# ProPrj_RF_Nano_Funbots_2025-01-09.net
KiCad netlist of a schematic drawn in EasyEDA Pro
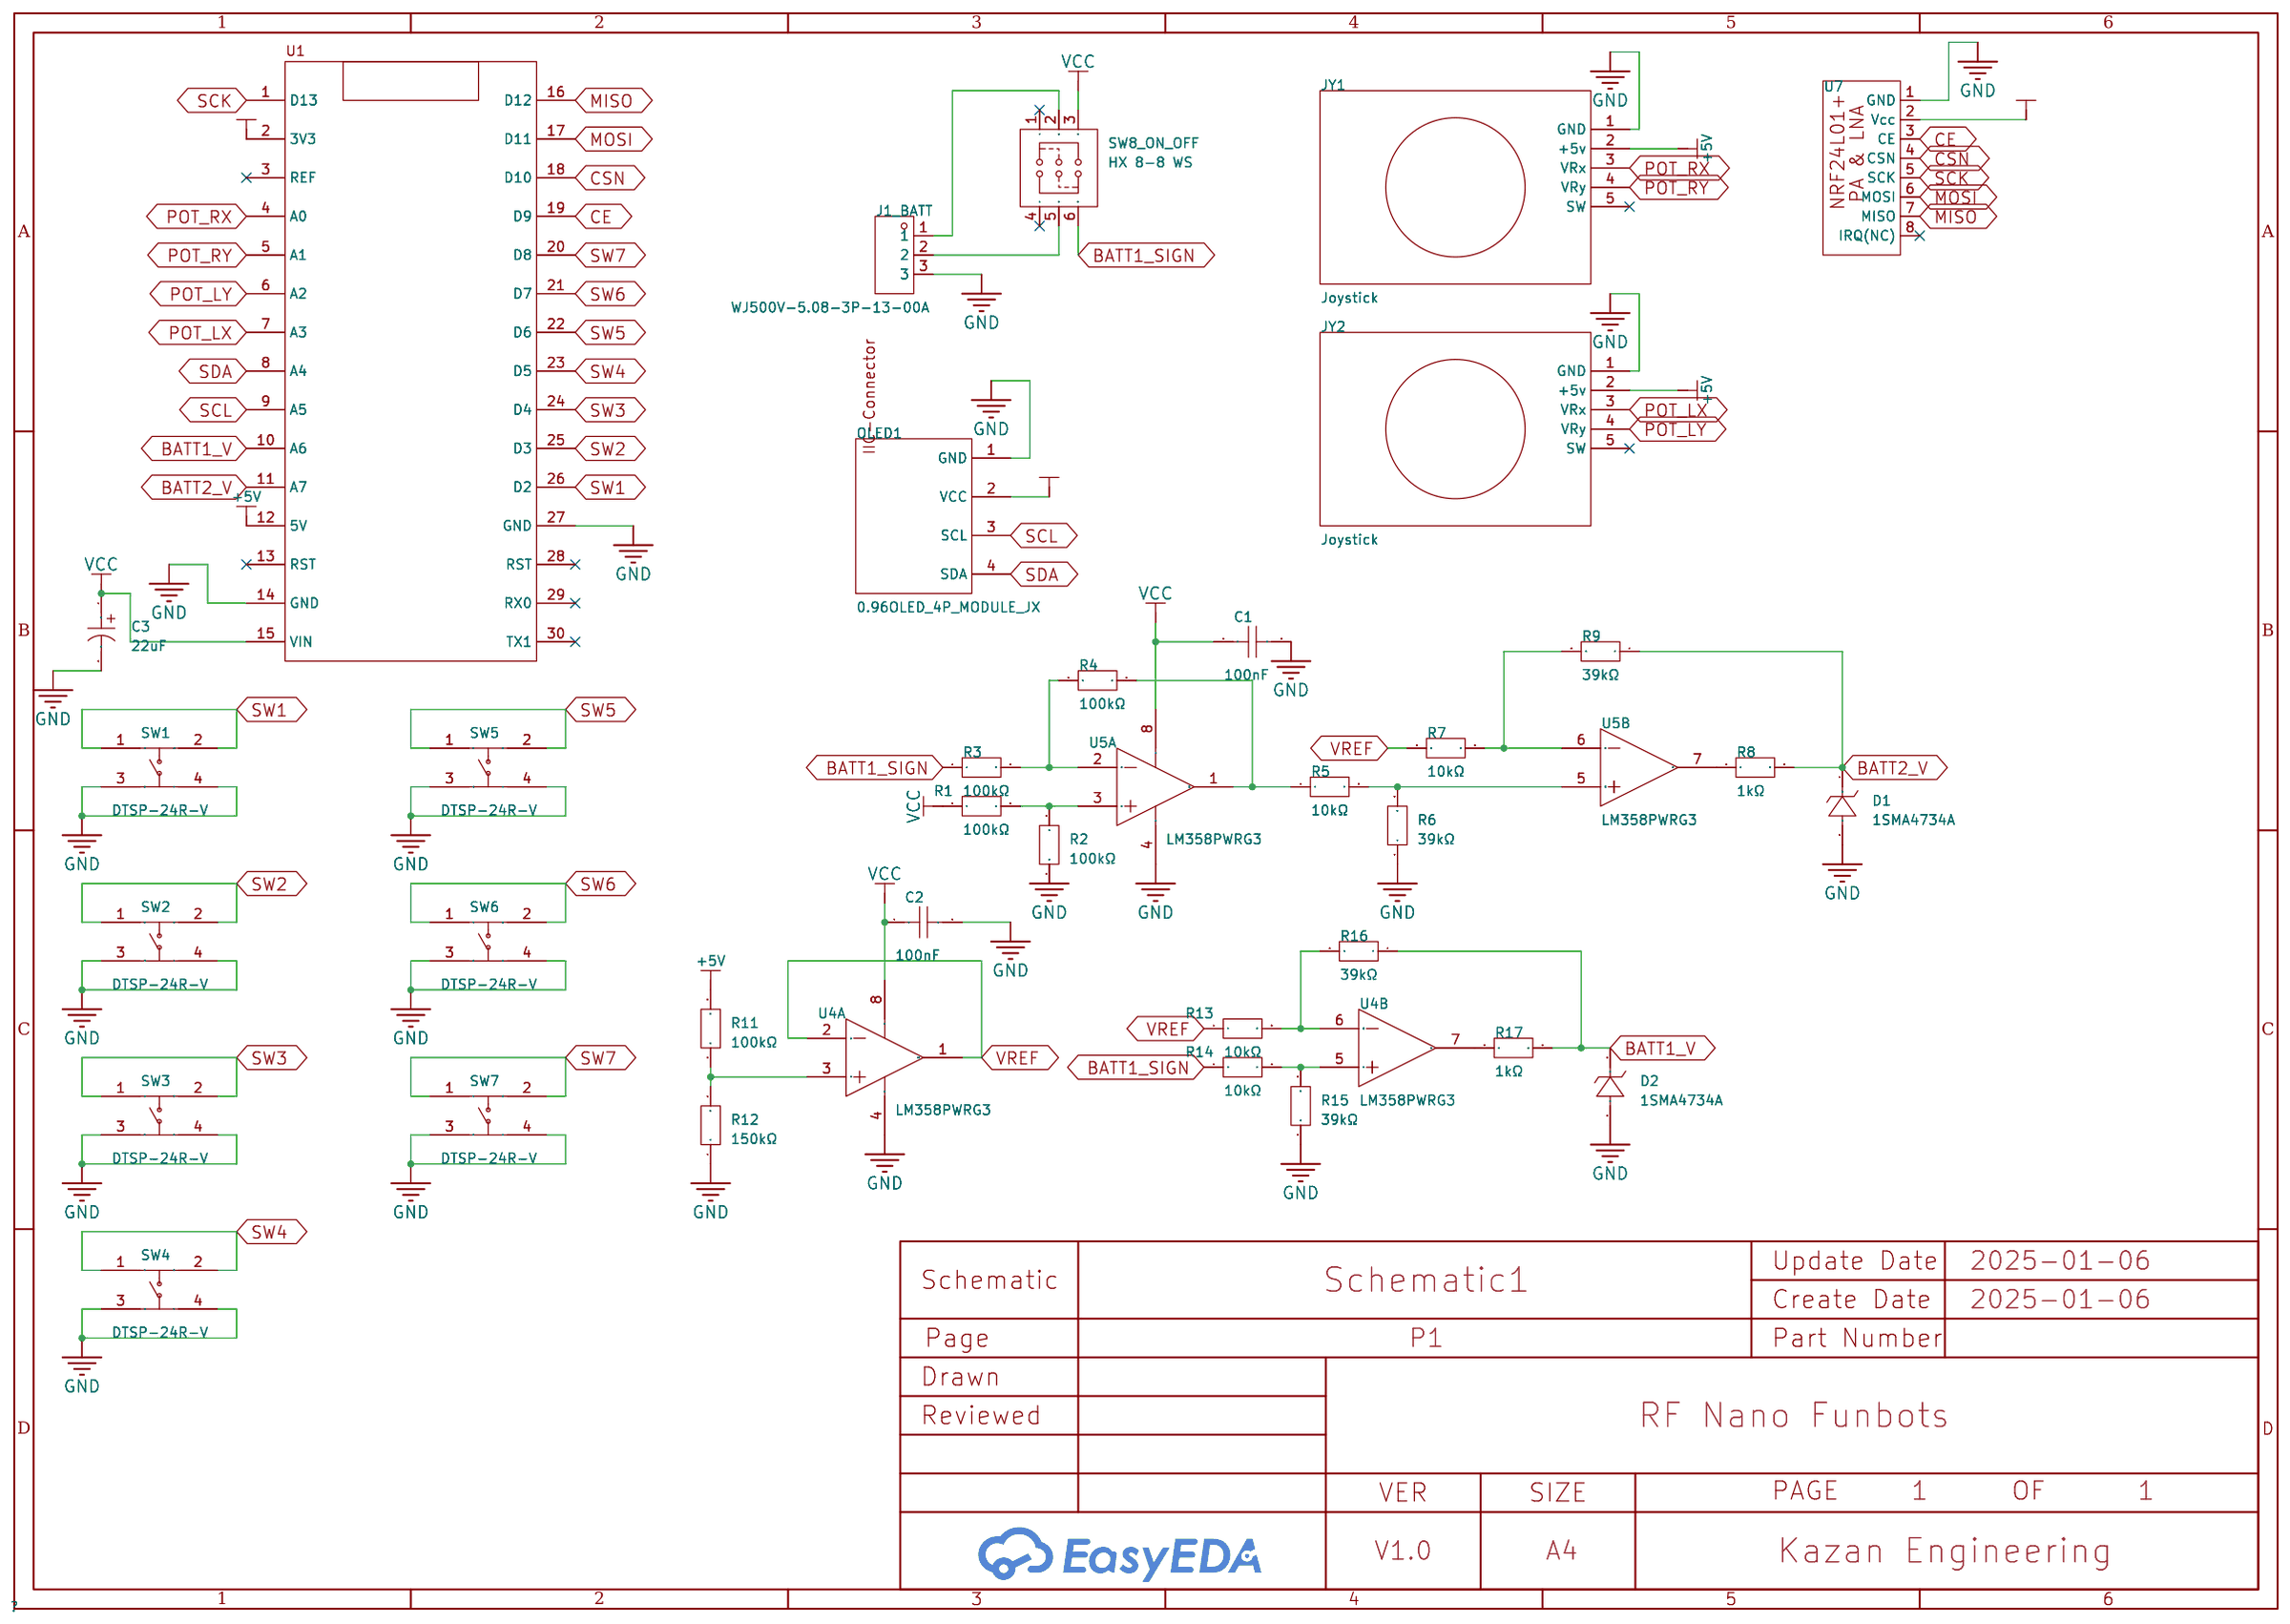
[diagram p0: schematic sheet]

(export (version "E")
  (design (tool "Eeschema 10.0.6"))
  (components
    (comp (ref "C1")
      (value "100nF")
      (footprint "easyedapro:C0805")
      (fields
        (field (name "Manufacturer Part") "FCC0805B104K500DT")
        (field (name "Manufacturer") "FOJAN(富捷)")
      )
      (libsource (lib "easyedapro") (part "FCC0805B104K500DT"))
    )
    (comp (ref "C2")
      (value "100nF")
      (footprint "easyedapro:C0805")
      (fields
        (field (name "Manufacturer Part") "FCC0805B104K500DT")
        (field (name "Manufacturer") "FOJAN(富捷)")
      )
      (libsource (lib "easyedapro") (part "FCC0805B104K500DT"))
    )
    (comp (ref "C3")
      (value "22uF")
      (footprint "easyedapro:CAP-TH_BD5.0-P2.00-D0.5-FD")
      (fields (field (name "Manufacturer Part") "CD1101HM220D110T") (field (name "Manufacturer") "创慧电子"))
      (libsource (lib "easyedapro") (part "CD1101HM220D110T"))
    )
    (comp (ref "D1")
      (value "1SMA4734A")
      (footprint "easyedapro:SMA_L4.3-W2.6-LS5.1-RD")
      (fields (field (name "Manufacturer") "YONGYUTAI(永裕泰)"))
      (libsource (lib "easyedapro") (part "1SMA4734A_C5128847"))
    )
    (comp (ref "D2")
      (value "1SMA4734A")
      (footprint "easyedapro:SMA_L4.3-W2.6-LS5.1-RD")
      (fields (field (name "Manufacturer") "YONGYUTAI(永裕泰)"))
      (libsource (lib "easyedapro") (part "1SMA4734A_C5128847"))
    )
    (comp (ref "J1_BATT")
      (value "WJ500V-5.08-3P-13-00A")
      (footprint "easyedapro:CONN-TH_3P-P5.00_WJ500V-5.08-3P")
      (fields (field (name "Manufacturer") "KANGNEX(康奈克斯电气)"))
      (libsource (lib "easyedapro") (part "WJ500V-5.08-3P-13-00A"))
    )
    (comp (ref "JY1")
      (value "Joystick")
      (footprint "easyedapro:JOYSTICK-2AXIS-BUTTON")
      (libsource (lib "easyedapro") (part "JoyStick_Arduino"))
    )
    (comp (ref "JY2")
      (value "Joystick")
      (footprint "easyedapro:JOYSTICK-2AXIS-BUTTON")
      (libsource (lib "easyedapro") (part "JoyStick_Arduino"))
    )
    (comp (ref "OLED1")
      (value "0.96OLED_4P_MODULE_JX")
      (footprint "easyedapro:0.96OLED_4P")
      (libsource (lib "easyedapro") (part "0.96OLED_4P_MODULE_JX"))
    )
    (comp (ref "R1")
      (value "100kΩ")
      (footprint "easyedapro:R0402")
      (fields
        (field (name "Manufacturer Part") "ERA-2VEB1003X")
        (field (name "Manufacturer") "PANASONIC(松下)")
      )
      (libsource (lib "easyedapro") (part "ERA-2VEB1003X"))
    )
    (comp (ref "R2")
      (value "100kΩ")
      (footprint "easyedapro:R0402")
      (fields
        (field (name "Manufacturer Part") "ERA-2VEB1003X")
        (field (name "Manufacturer") "PANASONIC(松下)")
      )
      (libsource (lib "easyedapro") (part "ERA-2VEB1003X"))
    )
    (comp (ref "R3")
      (value "100kΩ")
      (footprint "easyedapro:R0402")
      (fields
        (field (name "Manufacturer Part") "ERA-2VEB1003X")
        (field (name "Manufacturer") "PANASONIC(松下)")
      )
      (libsource (lib "easyedapro") (part "ERA-2VEB1003X"))
    )
    (comp (ref "R4")
      (value "100kΩ")
      (footprint "easyedapro:R0402")
      (fields
        (field (name "Manufacturer Part") "ERA-2VEB1003X")
        (field (name "Manufacturer") "PANASONIC(松下)")
      )
      (libsource (lib "easyedapro") (part "ERA-2VEB1003X"))
    )
    (comp (ref "R5")
      (value "10kΩ")
      (footprint "easyedapro:R1206")
      (fields (field (name "Manufacturer Part") "FRQ1206J103 TS") (field (name "Manufacturer") "FOJAN(富捷)"))
      (libsource (lib "easyedapro") (part "FRQ1206J103 TS"))
    )
    (comp (ref "R6")
      (value "39kΩ")
      (footprint "easyedapro:R1206")
      (fields (field (name "Manufacturer Part") "RT1206BRD0739KL") (field (name "Manufacturer") "YAGEO(国巨)"))
      (libsource (lib "easyedapro") (part "RT1206BRD0739KL"))
    )
    (comp (ref "R7")
      (value "10kΩ")
      (footprint "easyedapro:R1206")
      (fields (field (name "Manufacturer Part") "FRQ1206J103 TS") (field (name "Manufacturer") "FOJAN(富捷)"))
      (libsource (lib "easyedapro") (part "FRQ1206J103 TS"))
    )
    (comp (ref "R8")
      (value "1kΩ")
      (footprint "easyedapro:R0402")
      (fields (field (name "Manufacturer Part") "AC0402FR-7W1KL") (field (name "Manufacturer") "YAGEO(国巨)"))
      (libsource (lib "easyedapro") (part "AC0402FR-7W1KL"))
    )
    (comp (ref "R9")
      (value "39kΩ")
      (footprint "easyedapro:R1206")
      (fields (field (name "Manufacturer Part") "RT1206BRD0739KL") (field (name "Manufacturer") "YAGEO(国巨)"))
      (libsource (lib "easyedapro") (part "RT1206BRD0739KL"))
    )
    (comp (ref "R11")
      (value "100kΩ")
      (footprint "easyedapro:R0402")
      (fields
        (field (name "Manufacturer Part") "ERA-2VEB1003X")
        (field (name "Manufacturer") "PANASONIC(松下)")
      )
      (libsource (lib "easyedapro") (part "ERA-2VEB1003X"))
    )
    (comp (ref "R12")
      (value "150kΩ")
      (footprint "easyedapro:R0603")
      (fields (field (name "Manufacturer Part") "FRC0603F1503TS") (field (name "Manufacturer") "FOJAN(富捷)"))
      (libsource (lib "easyedapro") (part "FRC0603F1503TS"))
    )
    (comp (ref "R13")
      (value "10kΩ")
      (footprint "easyedapro:R1206")
      (fields (field (name "Manufacturer Part") "FRQ1206J103 TS") (field (name "Manufacturer") "FOJAN(富捷)"))
      (libsource (lib "easyedapro") (part "FRQ1206J103 TS"))
    )
    (comp (ref "R14")
      (value "10kΩ")
      (footprint "easyedapro:R1206")
      (fields (field (name "Manufacturer Part") "FRQ1206J103 TS") (field (name "Manufacturer") "FOJAN(富捷)"))
      (libsource (lib "easyedapro") (part "FRQ1206J103 TS"))
    )
    (comp (ref "R15")
      (value "39kΩ")
      (footprint "easyedapro:R1206")
      (fields (field (name "Manufacturer Part") "RT1206BRD0739KL") (field (name "Manufacturer") "YAGEO(国巨)"))
      (libsource (lib "easyedapro") (part "RT1206BRD0739KL"))
    )
    (comp (ref "R16")
      (value "39kΩ")
      (footprint "easyedapro:R1206")
      (fields (field (name "Manufacturer Part") "RT1206BRD0739KL") (field (name "Manufacturer") "YAGEO(国巨)"))
      (libsource (lib "easyedapro") (part "RT1206BRD0739KL"))
    )
    (comp (ref "R17")
      (value "1kΩ")
      (footprint "easyedapro:R0402")
      (fields (field (name "Manufacturer Part") "AC0402FR-7W1KL") (field (name "Manufacturer") "YAGEO(国巨)"))
      (libsource (lib "easyedapro") (part "AC0402FR-7W1KL"))
    )
    (comp (ref "SW1")
      (value "DTSP-24R-V")
      (footprint "easyedapro:SW-TH_4P-L12.0-W12.0-P5.00-LS13.0-EH")
      (libsource (lib "easyedapro") (part "DTSP-24R-V"))
    )
    (comp (ref "SW2")
      (value "DTSP-24R-V")
      (footprint "easyedapro:SW-TH_4P-L12.0-W12.0-P5.00-LS13.0-EH")
      (libsource (lib "easyedapro") (part "DTSP-24R-V"))
    )
    (comp (ref "SW3")
      (value "DTSP-24R-V")
      (footprint "easyedapro:SW-TH_4P-L12.0-W12.0-P5.00-LS13.0-EH")
      (libsource (lib "easyedapro") (part "DTSP-24R-V"))
    )
    (comp (ref "SW4")
      (value "DTSP-24R-V")
      (footprint "easyedapro:SW-TH_4P-L12.0-W12.0-P5.00-LS13.0-EH")
      (libsource (lib "easyedapro") (part "DTSP-24R-V"))
    )
    (comp (ref "SW5")
      (value "DTSP-24R-V")
      (footprint "easyedapro:SW-TH_4P-L12.0-W12.0-P5.00-LS13.0-EH")
      (libsource (lib "easyedapro") (part "DTSP-24R-V"))
    )
    (comp (ref "SW6")
      (value "DTSP-24R-V")
      (footprint "easyedapro:SW-TH_4P-L12.0-W12.0-P5.00-LS13.0-EH")
      (libsource (lib "easyedapro") (part "DTSP-24R-V"))
    )
    (comp (ref "SW7")
      (value "DTSP-24R-V")
      (footprint "easyedapro:SW-TH_4P-L12.0-W12.0-P5.00-LS13.0-EH")
      (libsource (lib "easyedapro") (part "DTSP-24R-V"))
    )
    (comp (ref "SW8_ON_OFF")
      (value "HX 8-8 WS")
      (footprint "easyedapro:SW-TH_HX-8-8-WS")
      (fields (field (name "Manufacturer") "hanxia(韩下)"))
      (libsource (lib "easyedapro") (part "HX 8-8 WS"))
    )
    (comp (ref "U1")
      (value "~")
      (footprint "easyedapro:COMM-TH_ARDUINO_NANO")
      (description "Arduino Nano")
      (libsource (lib "easyedapro") (part "Arduino Nano"))
    )
    (comp (ref "U4")
      (value "LM358PWRG3")
      (footprint "easyedapro:TSSOP-8_L4.4-W3.0-P0.65-LS6.4-BL")
      (fields (field (name "Manufacturer") "TI(德州仪器)"))
      (libsource (lib "easyedapro") (part "LM358PWRG3"))
    )
    (comp (ref "U5")
      (value "LM358PWRG3")
      (footprint "easyedapro:TSSOP-8_L4.4-W3.0-P0.65-LS6.4-BL")
      (fields (field (name "Manufacturer") "TI(德州仪器)"))
      (libsource (lib "easyedapro") (part "LM358PWRG3"))
    )
    (comp (ref "U7")
      (value "~")
      (footprint "easyedapro:NRF24L01+PA+LNA_PCB")
      (libsource (lib "easyedapro") (part "NRF24L01+PA+LNA"))
    )
  )
  (nets
    (net (code "1") (name "+3.3V") (class "Default")
      (node (ref "OLED1") (pin "2") (pinfunction "VCC_2") (pintype "input"))
      (node (ref "U1") (pin "2") (pinfunction "3V3_2") (pintype "input"))
      (node (ref "U7") (pin "2") (pinfunction "Vcc_2") (pintype "unspecified"))
    )
    (net (code "2") (name "+5V") (class "Default")
      (node (ref "JY1") (pin "2") (pinfunction "+5v_2") (pintype "input"))
      (node (ref "JY2") (pin "2") (pinfunction "+5v_2") (pintype "input"))
      (node (ref "R11") (pin "2") (pinfunction "2_2") (pintype "unspecified"))
      (node (ref "U1") (pin "12") (pinfunction "5V_12") (pintype "input"))
    )
    (net (code "3") (name "BATT1_SIGN") (class "Default")
      (node (ref "R14") (pin "1") (pinfunction "1_1") (pintype "unspecified"))
      (node (ref "R3") (pin "1") (pinfunction "1_1") (pintype "unspecified"))
      (node (ref "SW8_ON_OFF") (pin "6") (pinfunction "6_6") (pintype "unspecified"))
    )
    (net (code "4") (name "BATT1_V") (class "Default")
      (node (ref "D2") (pin "1") (pinfunction "C_1") (pintype "unspecified"))
      (node (ref "R16") (pin "1") (pinfunction "1_1") (pintype "unspecified"))
      (node (ref "R17") (pin "2") (pinfunction "2_2") (pintype "unspecified"))
      (node (ref "U1") (pin "10") (pinfunction "A6_10") (pintype "input"))
    )
    (net (code "5") (name "BATT2_V") (class "Default")
      (node (ref "D1") (pin "1") (pinfunction "C_1") (pintype "unspecified"))
      (node (ref "R8") (pin "2") (pinfunction "2_2") (pintype "unspecified"))
      (node (ref "R9") (pin "1") (pinfunction "1_1") (pintype "unspecified"))
      (node (ref "U1") (pin "11") (pinfunction "A7_11") (pintype "input"))
    )
    (net (code "6") (name "CE") (class "Default")
      (node (ref "U1") (pin "19") (pinfunction "D9_19") (pintype "input"))
      (node (ref "U7") (pin "3") (pinfunction "CE_3") (pintype "unspecified"))
    )
    (net (code "7") (name "CSN") (class "Default")
      (node (ref "U1") (pin "18") (pinfunction "D10_18") (pintype "input"))
      (node (ref "U7") (pin "4") (pinfunction "CSN_4") (pintype "unspecified"))
    )
    (net (code "8") (name "GND") (class "Default")
      (node (ref "C1") (pin "2") (pinfunction "2_2") (pintype "unspecified"))
      (node (ref "C2") (pin "2") (pinfunction "2_2") (pintype "unspecified"))
      (node (ref "C3") (pin "2") (pinfunction "2_2") (pintype "input"))
      (node (ref "D1") (pin "2") (pinfunction "A_2") (pintype "unspecified"))
      (node (ref "D2") (pin "2") (pinfunction "A_2") (pintype "unspecified"))
      (node (ref "J1_BATT") (pin "3") (pinfunction "3_3") (pintype "unspecified"))
      (node (ref "JY1") (pin "1") (pinfunction "GND_1") (pintype "input"))
      (node (ref "JY2") (pin "1") (pinfunction "GND_1") (pintype "input"))
      (node (ref "OLED1") (pin "1") (pinfunction "GND_1") (pintype "input"))
      (node (ref "R12") (pin "1") (pinfunction "1_1") (pintype "unspecified"))
      (node (ref "R15") (pin "1") (pinfunction "1_1") (pintype "unspecified"))
      (node (ref "R2") (pin "1") (pinfunction "1_1") (pintype "unspecified"))
      (node (ref "R6") (pin "1") (pinfunction "1_1") (pintype "unspecified"))
      (node (ref "SW1") (pin "3") (pinfunction "3_3") (pintype "unspecified"))
      (node (ref "SW1") (pin "4") (pinfunction "4_4") (pintype "unspecified"))
      (node (ref "SW2") (pin "3") (pinfunction "3_3") (pintype "unspecified"))
      (node (ref "SW2") (pin "4") (pinfunction "4_4") (pintype "unspecified"))
      (node (ref "SW3") (pin "3") (pinfunction "3_3") (pintype "unspecified"))
      (node (ref "SW3") (pin "4") (pinfunction "4_4") (pintype "unspecified"))
      (node (ref "SW4") (pin "3") (pinfunction "3_3") (pintype "unspecified"))
      (node (ref "SW4") (pin "4") (pinfunction "4_4") (pintype "unspecified"))
      (node (ref "SW5") (pin "3") (pinfunction "3_3") (pintype "unspecified"))
      (node (ref "SW5") (pin "4") (pinfunction "4_4") (pintype "unspecified"))
      (node (ref "SW6") (pin "3") (pinfunction "3_3") (pintype "unspecified"))
      (node (ref "SW6") (pin "4") (pinfunction "4_4") (pintype "unspecified"))
      (node (ref "SW7") (pin "3") (pinfunction "3_3") (pintype "unspecified"))
      (node (ref "SW7") (pin "4") (pinfunction "4_4") (pintype "unspecified"))
      (node (ref "U1") (pin "14") (pinfunction "GND_14") (pintype "input"))
      (node (ref "U1") (pin "27") (pinfunction "GND_27") (pintype "input"))
      (node (ref "U4") (pin "4") (pinfunction "V-_4") (pintype "unspecified"))
      (node (ref "U5") (pin "4") (pinfunction "V-_4") (pintype "unspecified"))
      (node (ref "U7") (pin "1") (pinfunction "GND_1") (pintype "unspecified"))
    )
    (net (code "9") (name "MISO") (class "Default")
      (node (ref "U1") (pin "16") (pinfunction "D12_16") (pintype "input"))
      (node (ref "U7") (pin "7") (pinfunction "MISO_7") (pintype "unspecified"))
    )
    (net (code "10") (name "MOSI") (class "Default")
      (node (ref "U1") (pin "17") (pinfunction "D11_17") (pintype "input"))
      (node (ref "U7") (pin "6") (pinfunction "MOSI_6") (pintype "unspecified"))
    )
    (net (code "11") (name "Net-(J1_BATT-Pad1)") (class "Default")
      (node (ref "J1_BATT") (pin "1") (pinfunction "1_1") (pintype "unspecified"))
      (node (ref "SW8_ON_OFF") (pin "2") (pinfunction "2_2") (pintype "unspecified"))
    )
    (net (code "12") (name "Net-(J1_BATT-Pad2)") (class "Default")
      (node (ref "J1_BATT") (pin "2") (pinfunction "2_2") (pintype "unspecified"))
      (node (ref "SW8_ON_OFF") (pin "5") (pinfunction "5_5") (pintype "unspecified"))
    )
    (net (code "13") (name "Net-(U4A-IN1+)") (class "Default")
      (node (ref "R11") (pin "1") (pinfunction "1_1") (pintype "unspecified"))
      (node (ref "R12") (pin "2") (pinfunction "2_2") (pintype "unspecified"))
      (node (ref "U4") (pin "3") (pinfunction "IN1+_3") (pintype "unspecified"))
    )
    (net (code "14") (name "Net-(U4B-IN2+)") (class "Default")
      (node (ref "R14") (pin "2") (pinfunction "2_2") (pintype "unspecified"))
      (node (ref "R15") (pin "2") (pinfunction "2_2") (pintype "unspecified"))
      (node (ref "U4") (pin "5") (pinfunction "IN2+_5") (pintype "unspecified"))
    )
    (net (code "15") (name "Net-(U4B-IN2-)") (class "Default")
      (node (ref "R13") (pin "2") (pinfunction "2_2") (pintype "unspecified"))
      (node (ref "R16") (pin "2") (pinfunction "2_2") (pintype "unspecified"))
      (node (ref "U4") (pin "6") (pinfunction "IN2-_6") (pintype "unspecified"))
    )
    (net (code "16") (name "Net-(U4B-OUT2)") (class "Default")
      (node (ref "R17") (pin "1") (pinfunction "1_1") (pintype "unspecified"))
      (node (ref "U4") (pin "7") (pinfunction "OUT2_7") (pintype "unspecified"))
    )
    (net (code "17") (name "Net-(U5A-IN1+)") (class "Default")
      (node (ref "R1") (pin "2") (pinfunction "2_2") (pintype "unspecified"))
      (node (ref "R2") (pin "2") (pinfunction "2_2") (pintype "unspecified"))
      (node (ref "U5") (pin "3") (pinfunction "IN1+_3") (pintype "unspecified"))
    )
    (net (code "18") (name "Net-(U5A-IN1-)") (class "Default")
      (node (ref "R3") (pin "2") (pinfunction "2_2") (pintype "unspecified"))
      (node (ref "R4") (pin "1") (pinfunction "1_1") (pintype "unspecified"))
      (node (ref "U5") (pin "2") (pinfunction "IN1-_2") (pintype "unspecified"))
    )
    (net (code "19") (name "Net-(U5A-OUT1)") (class "Default")
      (node (ref "R4") (pin "2") (pinfunction "2_2") (pintype "unspecified"))
      (node (ref "R5") (pin "1") (pinfunction "1_1") (pintype "unspecified"))
      (node (ref "U5") (pin "1") (pinfunction "OUT1_1") (pintype "unspecified"))
    )
    (net (code "20") (name "Net-(U5B-IN2+)") (class "Default")
      (node (ref "R5") (pin "2") (pinfunction "2_2") (pintype "unspecified"))
      (node (ref "R6") (pin "2") (pinfunction "2_2") (pintype "unspecified"))
      (node (ref "U5") (pin "5") (pinfunction "IN2+_5") (pintype "unspecified"))
    )
    (net (code "21") (name "Net-(U5B-IN2-)") (class "Default")
      (node (ref "R7") (pin "2") (pinfunction "2_2") (pintype "unspecified"))
      (node (ref "R9") (pin "2") (pinfunction "2_2") (pintype "unspecified"))
      (node (ref "U5") (pin "6") (pinfunction "IN2-_6") (pintype "unspecified"))
    )
    (net (code "22") (name "Net-(U5B-OUT2)") (class "Default")
      (node (ref "R8") (pin "1") (pinfunction "1_1") (pintype "unspecified"))
      (node (ref "U5") (pin "7") (pinfunction "OUT2_7") (pintype "unspecified"))
    )
    (net (code "23") (name "POT_LX") (class "Default")
      (node (ref "JY2") (pin "3") (pinfunction "VRx_3") (pintype "input"))
      (node (ref "U1") (pin "7") (pinfunction "A3_7") (pintype "input"))
    )
    (net (code "24") (name "POT_LY") (class "Default")
      (node (ref "JY2") (pin "4") (pinfunction "VRy_4") (pintype "input"))
      (node (ref "U1") (pin "6") (pinfunction "A2_6") (pintype "input"))
    )
    (net (code "25") (name "POT_RX") (class "Default")
      (node (ref "JY1") (pin "3") (pinfunction "VRx_3") (pintype "input"))
      (node (ref "U1") (pin "4") (pinfunction "A0_4") (pintype "input"))
    )
    (net (code "26") (name "POT_RY") (class "Default")
      (node (ref "JY1") (pin "4") (pinfunction "VRy_4") (pintype "input"))
      (node (ref "U1") (pin "5") (pinfunction "A1_5") (pintype "input"))
    )
    (net (code "27") (name "SCK") (class "Default")
      (node (ref "U1") (pin "1") (pinfunction "D13_1") (pintype "input"))
      (node (ref "U7") (pin "5") (pinfunction "SCK_5") (pintype "unspecified"))
    )
    (net (code "28") (name "SCL") (class "Default")
      (node (ref "OLED1") (pin "3") (pinfunction "SCL_3") (pintype "input"))
      (node (ref "U1") (pin "9") (pinfunction "A5_9") (pintype "input"))
    )
    (net (code "29") (name "SDA") (class "Default")
      (node (ref "OLED1") (pin "4") (pinfunction "SDA_4") (pintype "input"))
      (node (ref "U1") (pin "8") (pinfunction "A4_8") (pintype "input"))
    )
    (net (code "30") (name "SW1") (class "Default")
      (node (ref "SW1") (pin "1") (pinfunction "1_1") (pintype "unspecified"))
      (node (ref "SW1") (pin "2") (pinfunction "2_2") (pintype "unspecified"))
      (node (ref "U1") (pin "26") (pinfunction "D2_26") (pintype "input"))
    )
    (net (code "31") (name "SW2") (class "Default")
      (node (ref "SW2") (pin "1") (pinfunction "1_1") (pintype "unspecified"))
      (node (ref "SW2") (pin "2") (pinfunction "2_2") (pintype "unspecified"))
      (node (ref "U1") (pin "25") (pinfunction "D3_25") (pintype "input"))
    )
    (net (code "32") (name "SW3") (class "Default")
      (node (ref "SW3") (pin "1") (pinfunction "1_1") (pintype "unspecified"))
      (node (ref "SW3") (pin "2") (pinfunction "2_2") (pintype "unspecified"))
      (node (ref "U1") (pin "24") (pinfunction "D4_24") (pintype "input"))
    )
    (net (code "33") (name "SW4") (class "Default")
      (node (ref "SW4") (pin "1") (pinfunction "1_1") (pintype "unspecified"))
      (node (ref "SW4") (pin "2") (pinfunction "2_2") (pintype "unspecified"))
      (node (ref "U1") (pin "23") (pinfunction "D5_23") (pintype "input"))
    )
    (net (code "34") (name "SW5") (class "Default")
      (node (ref "SW5") (pin "1") (pinfunction "1_1") (pintype "unspecified"))
      (node (ref "SW5") (pin "2") (pinfunction "2_2") (pintype "unspecified"))
      (node (ref "U1") (pin "22") (pinfunction "D6_22") (pintype "input"))
    )
    (net (code "35") (name "SW6") (class "Default")
      (node (ref "SW6") (pin "1") (pinfunction "1_1") (pintype "unspecified"))
      (node (ref "SW6") (pin "2") (pinfunction "2_2") (pintype "unspecified"))
      (node (ref "U1") (pin "21") (pinfunction "D7_21") (pintype "input"))
    )
    (net (code "36") (name "SW7") (class "Default")
      (node (ref "SW7") (pin "1") (pinfunction "1_1") (pintype "unspecified"))
      (node (ref "SW7") (pin "2") (pinfunction "2_2") (pintype "unspecified"))
      (node (ref "U1") (pin "20") (pinfunction "D8_20") (pintype "input"))
    )
    (net (code "37") (name "VCC") (class "Default")
      (node (ref "C1") (pin "1") (pinfunction "1_1") (pintype "unspecified"))
      (node (ref "C2") (pin "1") (pinfunction "1_1") (pintype "unspecified"))
      (node (ref "C3") (pin "1") (pinfunction "1_1") (pintype "input"))
      (node (ref "R1") (pin "1") (pinfunction "1_1") (pintype "unspecified"))
      (node (ref "SW8_ON_OFF") (pin "3") (pinfunction "3_3") (pintype "unspecified"))
      (node (ref "U1") (pin "15") (pinfunction "VIN_15") (pintype "input"))
      (node (ref "U4") (pin "8") (pinfunction "V+_8") (pintype "unspecified"))
      (node (ref "U5") (pin "8") (pinfunction "V+_8") (pintype "unspecified"))
    )
    (net (code "38") (name "VREF") (class "Default")
      (node (ref "R13") (pin "1") (pinfunction "1_1") (pintype "unspecified"))
      (node (ref "R7") (pin "1") (pinfunction "1_1") (pintype "unspecified"))
      (node (ref "U4") (pin "1") (pinfunction "OUT1_1") (pintype "unspecified"))
      (node (ref "U4") (pin "2") (pinfunction "IN1-_2") (pintype "unspecified"))
    )
    (net (code "39") (name "unconnected-(JY1-SW-Pad5)") (class "Default")
      (node (ref "JY1") (pin "5") (pinfunction "SW_5") (pintype "input+no_connect"))
    )
    (net (code "40") (name "unconnected-(JY2-SW-Pad5)") (class "Default")
      (node (ref "JY2") (pin "5") (pinfunction "SW_5") (pintype "input+no_connect"))
    )
    (net (code "41") (name "unconnected-(SW8_ON_OFF-Pad1)") (class "Default")
      (node (ref "SW8_ON_OFF") (pin "1") (pinfunction "1_1") (pintype "unspecified+no_connect"))
    )
    (net (code "42") (name "unconnected-(SW8_ON_OFF-Pad4)") (class "Default")
      (node (ref "SW8_ON_OFF") (pin "4") (pinfunction "4_4") (pintype "unspecified+no_connect"))
    )
    (net (code "43") (name "unconnected-(U1-REF-Pad3)") (class "Default")
      (node (ref "U1") (pin "3") (pinfunction "REF_3") (pintype "input+no_connect"))
    )
    (net (code "44") (name "unconnected-(U1-RST-Pad13)") (class "Default")
      (node (ref "U1") (pin "13") (pinfunction "RST_13") (pintype "input+no_connect"))
    )
    (net (code "45") (name "unconnected-(U1-RST-Pad28)") (class "Default")
      (node (ref "U1") (pin "28") (pinfunction "RST_28") (pintype "input+no_connect"))
    )
    (net (code "46") (name "unconnected-(U1-RX0-Pad29)") (class "Default")
      (node (ref "U1") (pin "29") (pinfunction "RX0_29") (pintype "input+no_connect"))
    )
    (net (code "47") (name "unconnected-(U1-TX1-Pad30)") (class "Default")
      (node (ref "U1") (pin "30") (pinfunction "TX1_30") (pintype "input+no_connect"))
    )
    (net (code "48") (name "unconnected-(U7-IRQ(NC)-Pad8)") (class "Default")
      (node (ref "U7") (pin "8") (pinfunction "IRQ(NC)_8") (pintype "unspecified+no_connect"))
    )
  )
)
